# 02_Sensors.net
KiCad netlist of a schematic drawn in Altium Designer
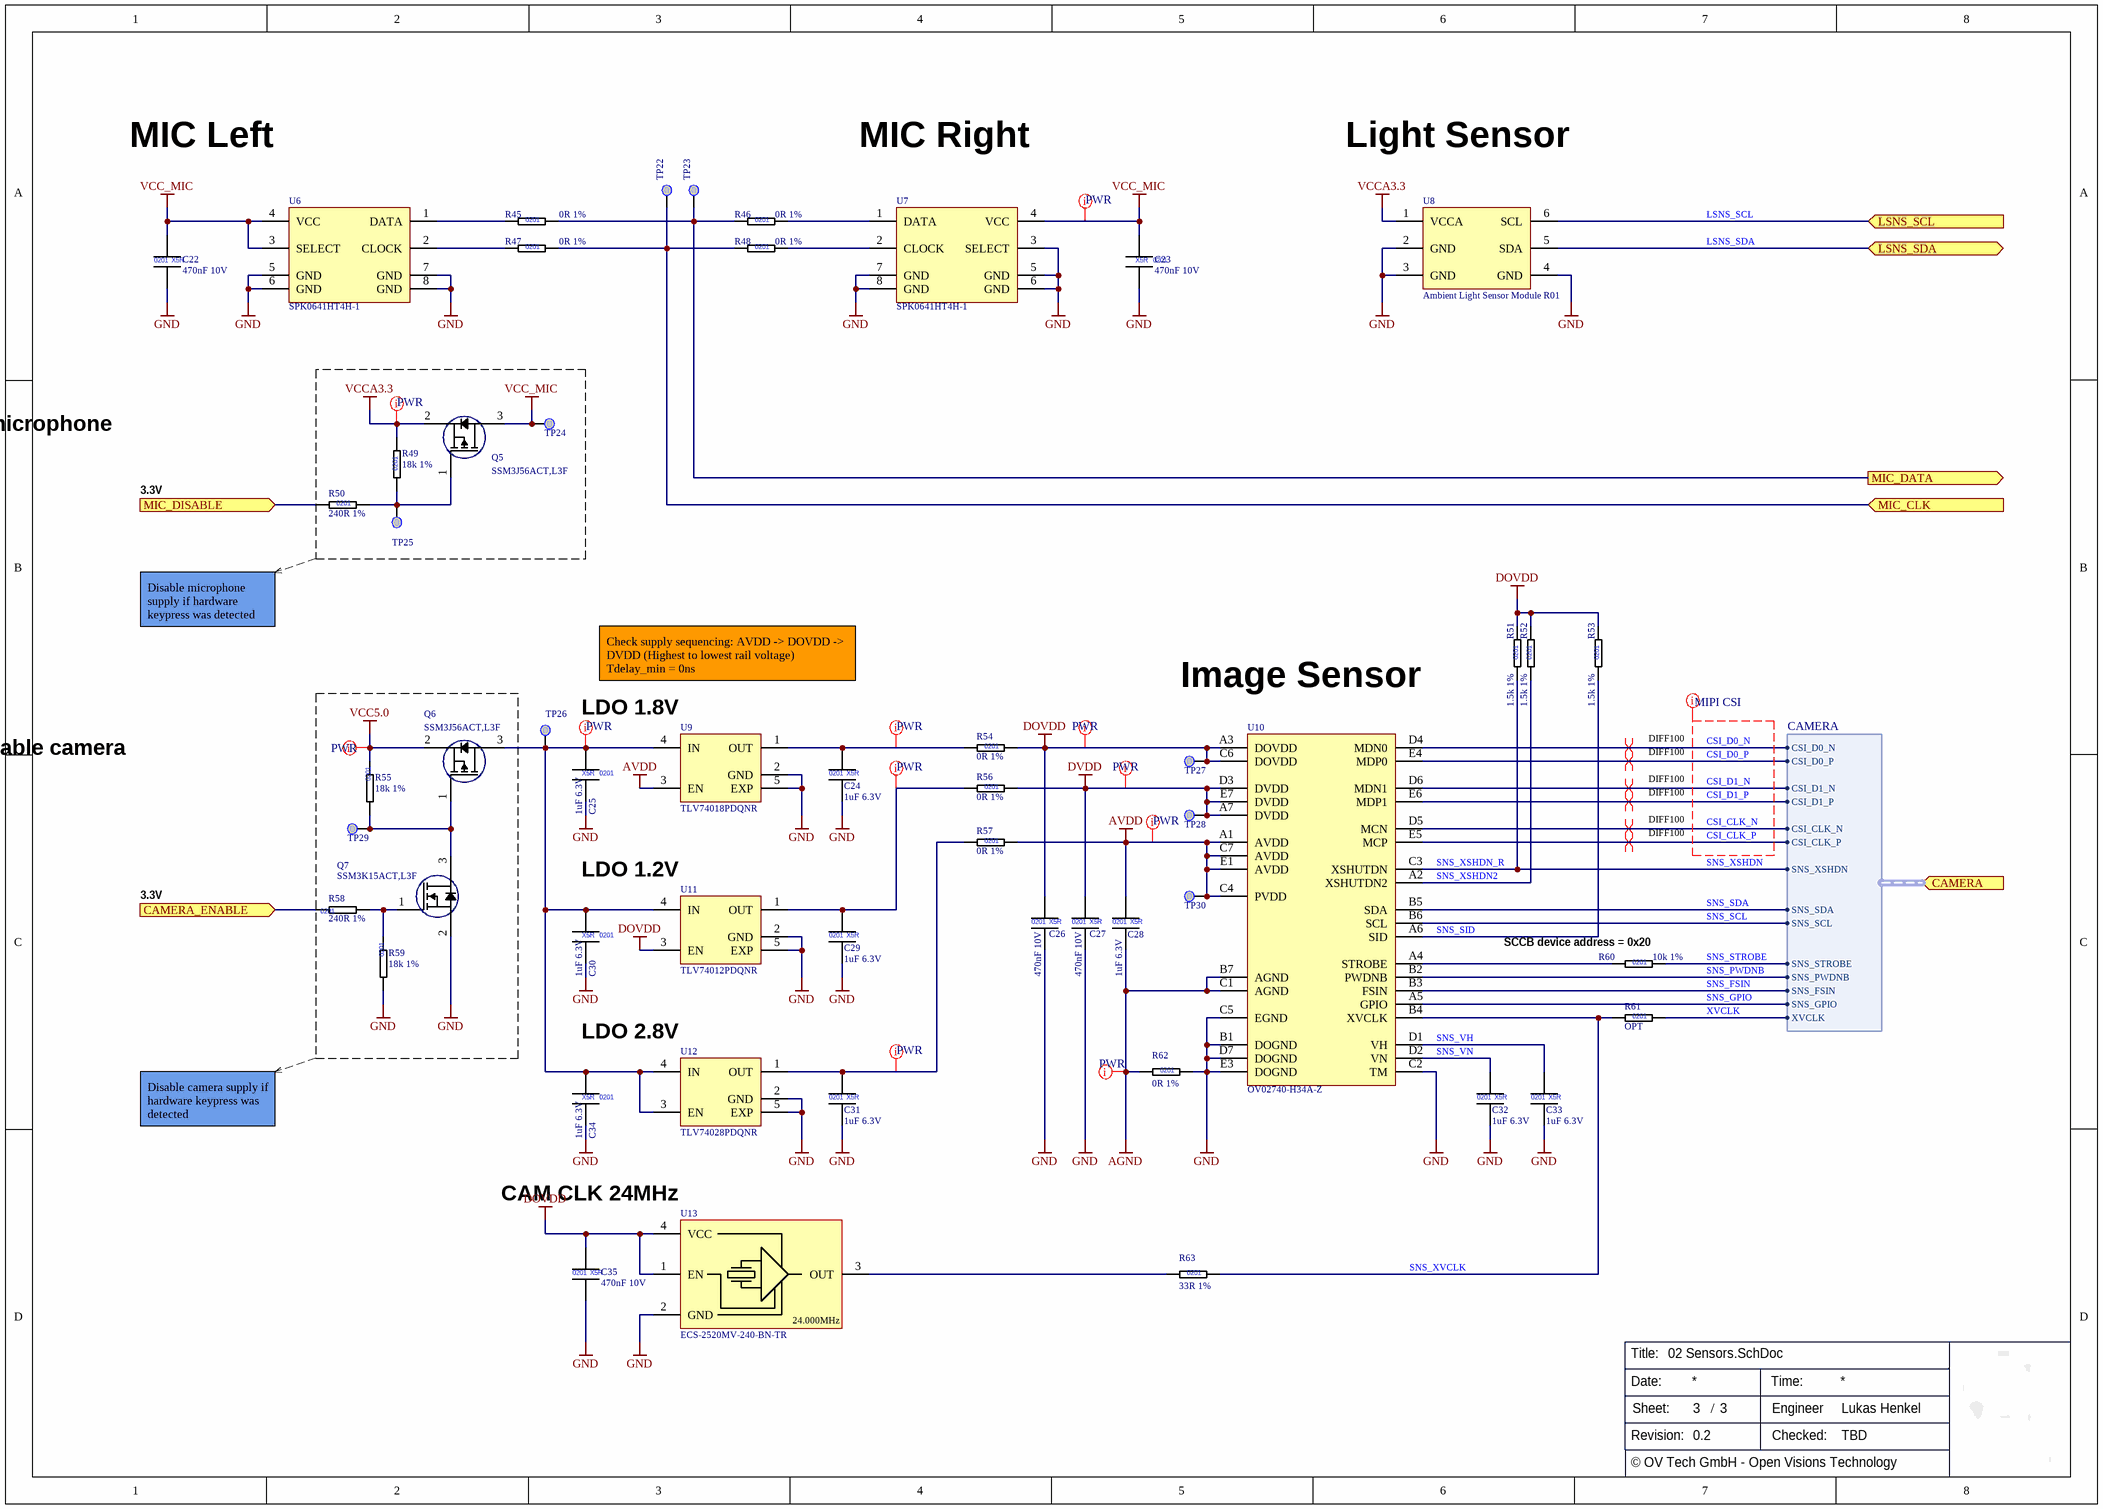
[diagram p0: 02 Sensors.SchDoc]

(export (version "E")
  (design (tool "Eeschema 10.0.6"))
  (components
    (comp (ref "C22")
      (value "470nF 10V")
      (footprint "QV_Cap:CAPC0603X03L")
      (description "Multilayer Ceramic Capacitors MLCC - SMD/SMT 0201 10VDC")
      (libsource (lib "QV_Cap") (part "CAP_0201_470nF_10V"))
    )
    (comp (ref "C23")
      (value "470nF 10V")
      (footprint "QV_Cap:CAPC0603X03L")
      (description "Multilayer Ceramic Capacitors MLCC - SMD/SMT 0201 10VDC")
      (libsource (lib "QV_Cap") (part "CAP_0201_470nF_10V"))
    )
    (comp (ref "C24")
      (value "1uF 6.3V")
      (footprint "QV_Cap:CAPC0603X03L")
      (description "Multilayer Ceramic Capacitors MLCC - SMD/SMT 0201 6.3VDC")
      (libsource (lib "QV_Cap") (part "CAP_0201_1uF_6.3V"))
    )
    (comp (ref "C25")
      (value "1uF 6.3V")
      (footprint "QV_Cap:CAPC0603X03L")
      (description "Multilayer Ceramic Capacitors MLCC - SMD/SMT 0201 6.3VDC")
      (libsource (lib "QV_Cap") (part "CAP_0201_1uF_6.3V"))
    )
    (comp (ref "C26")
      (value "470nF 10V")
      (footprint "QV_Cap:CAPC0603X03L")
      (description "Multilayer Ceramic Capacitors MLCC - SMD/SMT 0201 10VDC")
      (libsource (lib "QV_Cap") (part "CAP_0201_470nF_10V"))
    )
    (comp (ref "C27")
      (value "470nF 10V")
      (footprint "QV_Cap:CAPC0603X03L")
      (description "Multilayer Ceramic Capacitors MLCC - SMD/SMT 0201 10VDC")
      (libsource (lib "QV_Cap") (part "CAP_0201_470nF_10V"))
    )
    (comp (ref "C28")
      (value "1uF 6.3V")
      (footprint "QV_Cap:CAPC0603X03L")
      (description "Multilayer Ceramic Capacitors MLCC - SMD/SMT 0201 6.3VDC")
      (libsource (lib "QV_Cap") (part "CAP_0201_1uF_6.3V"))
    )
    (comp (ref "C29")
      (value "1uF 6.3V")
      (footprint "QV_Cap:CAPC0603X03L")
      (description "Multilayer Ceramic Capacitors MLCC - SMD/SMT 0201 6.3VDC")
      (libsource (lib "QV_Cap") (part "CAP_0201_1uF_6.3V"))
    )
    (comp (ref "C30")
      (value "1uF 6.3V")
      (footprint "QV_Cap:CAPC0603X03L")
      (description "Multilayer Ceramic Capacitors MLCC - SMD/SMT 0201 6.3VDC")
      (libsource (lib "QV_Cap") (part "CAP_0201_1uF_6.3V"))
    )
    (comp (ref "C31")
      (value "1uF 6.3V")
      (footprint "QV_Cap:CAPC0603X03L")
      (description "Multilayer Ceramic Capacitors MLCC - SMD/SMT 0201 6.3VDC")
      (libsource (lib "QV_Cap") (part "CAP_0201_1uF_6.3V"))
    )
    (comp (ref "C32")
      (value "1uF 6.3V")
      (footprint "QV_Cap:CAPC0603X03L")
      (description "Multilayer Ceramic Capacitors MLCC - SMD/SMT 0201 6.3VDC")
      (libsource (lib "QV_Cap") (part "CAP_0201_1uF_6.3V"))
    )
    (comp (ref "C33")
      (value "1uF 6.3V")
      (footprint "QV_Cap:CAPC0603X03L")
      (description "Multilayer Ceramic Capacitors MLCC - SMD/SMT 0201 6.3VDC")
      (libsource (lib "QV_Cap") (part "CAP_0201_1uF_6.3V"))
    )
    (comp (ref "C34")
      (value "1uF 6.3V")
      (footprint "QV_Cap:CAPC0603X03L")
      (description "Multilayer Ceramic Capacitors MLCC - SMD/SMT 0201 6.3VDC")
      (libsource (lib "QV_Cap") (part "CAP_0201_1uF_6.3V"))
    )
    (comp (ref "C35")
      (value "470nF 10V")
      (footprint "QV_Cap:CAPC0603X03L")
      (description "Multilayer Ceramic Capacitors MLCC - SMD/SMT 0201 10VDC")
      (libsource (lib "QV_Cap") (part "CAP_0201_470nF_10V"))
    )
    (comp (ref "Q5")
      (value "SSM3J56ACT,L3F")
      (footprint "QV_Trans:DFN65P100X50-3L")
      (description "MOSFET 20V SGL P-CH TRENCHMOS Logic Level")
      (libsource (lib "QV_Trans") (part "P-Channel MOSFET_SSM3J56ACT,L3F"))
    )
    (comp (ref "Q6")
      (value "SSM3J56ACT,L3F")
      (footprint "QV_Trans:DFN65P100X50-3L")
      (description "MOSFET 20V SGL P-CH TRENCHMOS Logic Level")
      (libsource (lib "QV_Trans") (part "P-Channel MOSFET_SSM3J56ACT,L3F"))
    )
    (comp (ref "Q7")
      (value "SSM3K15ACT,L3F")
      (footprint "QV_Trans:DFN65P100X50-3L")
      (description "MOSFET 30V SGL N-CH TRENCHMOS Logic Level")
      (libsource (lib "QV_Trans") (part "N-Channel MOSFET_SSM3K15ACT,L3F"))
    )
    (comp (ref "R45")
      (value "0R 1%")
      (footprint "QV_Res:RESC0603X03L")
      (description "Thick Film Resistors - SMD 0R OHM 1%")
      (libsource (lib "QV_res") (part "RES_0201_0R_1%"))
    )
    (comp (ref "R46")
      (value "0R 1%")
      (footprint "QV_Res:RESC0603X03L")
      (description "Thick Film Resistors - SMD 0R OHM 1%")
      (libsource (lib "QV_res") (part "RES_0201_0R_1%"))
    )
    (comp (ref "R47")
      (value "0R 1%")
      (footprint "QV_Res:RESC0603X03L")
      (description "Thick Film Resistors - SMD 0R OHM 1%")
      (libsource (lib "QV_res") (part "RES_0201_0R_1%"))
    )
    (comp (ref "R48")
      (value "0R 1%")
      (footprint "QV_Res:RESC0603X03L")
      (description "Thick Film Resistors - SMD 0R OHM 1%")
      (libsource (lib "QV_res") (part "RES_0201_0R_1%"))
    )
    (comp (ref "R49")
      (value "18k 1%")
      (footprint "QV_Res:RESC0603X03L")
      (description "Thick Film Resistors - SMD 18K OHM 1%")
      (libsource (lib "QV_res") (part "RES_0201_18k_1%"))
    )
    (comp (ref "R50")
      (value "240R 1%")
      (footprint "QV_Res:RESC0603X03L")
      (description "Thick Film Resistors - SMD 240 OHM 1%")
      (libsource (lib "QV_res") (part "RES_0201_240R_1%"))
    )
    (comp (ref "R51")
      (value "1.5k 1%")
      (footprint "QV_Res:RESC0603X03L")
      (description "Thick Film Resistors - SMD 1.5K OHM 1%")
      (libsource (lib "QV_res") (part "RES_0201_1.5k_1%"))
    )
    (comp (ref "R52")
      (value "1.5k 1%")
      (footprint "QV_Res:RESC0603X03L")
      (description "Thick Film Resistors - SMD 1.5K OHM 1%")
      (libsource (lib "QV_res") (part "RES_0201_1.5k_1%"))
    )
    (comp (ref "R53")
      (value "1.5k 1%")
      (footprint "QV_Res:RESC0603X03L")
      (description "Thick Film Resistors - SMD 1.5K OHM 1%")
      (libsource (lib "QV_res") (part "RES_0201_1.5k_1%"))
    )
    (comp (ref "R54")
      (value "0R 1%")
      (footprint "QV_Res:RESC0603X03L")
      (description "Thick Film Resistors - SMD 0R OHM 1%")
      (libsource (lib "QV_res") (part "RES_0201_0R_1%"))
    )
    (comp (ref "R55")
      (value "18k 1%")
      (footprint "QV_Res:RESC0603X03L")
      (description "Thick Film Resistors - SMD 18K OHM 1%")
      (libsource (lib "QV_res") (part "RES_0201_18k_1%"))
    )
    (comp (ref "R56")
      (value "0R 1%")
      (footprint "QV_Res:RESC0603X03L")
      (description "Thick Film Resistors - SMD 0R OHM 1%")
      (libsource (lib "QV_res") (part "RES_0201_0R_1%"))
    )
    (comp (ref "R57")
      (value "0R 1%")
      (footprint "QV_Res:RESC0603X03L")
      (description "Thick Film Resistors - SMD 0R OHM 1%")
      (libsource (lib "QV_res") (part "RES_0201_0R_1%"))
    )
    (comp (ref "R58")
      (value "240R 1%")
      (footprint "QV_Res:RESC0603X03L")
      (description "Thick Film Resistors - SMD 240 OHM 1%")
      (libsource (lib "QV_res") (part "RES_0201_240R_1%"))
    )
    (comp (ref "R59")
      (value "18k 1%")
      (footprint "QV_Res:RESC0603X03L")
      (description "Thick Film Resistors - SMD 18K OHM 1%")
      (libsource (lib "QV_res") (part "RES_0201_18k_1%"))
    )
    (comp (ref "R60")
      (value "10k 1%")
      (footprint "QV_Res:RESC0603X03L")
      (description "Thick Film Resistors - SMD 10K OHM 1%")
      (libsource (lib "QV_res") (part "RES_0201_10k_1%"))
    )
    (comp (ref "R61")
      (value "OPT")
      (footprint "QV_Res:RESC0603X03L")
      (description "Thick Film Resistors - SMD Optinal")
      (libsource (lib "QV_res") (part "RES_0201_OPT"))
    )
    (comp (ref "R62")
      (value "0R 1%")
      (footprint "QV_Res:RESC0603X03L")
      (description "Thick Film Resistors - SMD 0R OHM 1%")
      (libsource (lib "QV_res") (part "RES_0201_0R_1%"))
    )
    (comp (ref "R63")
      (value "33R 1%")
      (footprint "QV_Res:RESC0603X03L")
      (description "Thick Film Resistors - SMD 33R OHM 1%")
      (libsource (lib "QV_res") (part "RES_0201_33R_1%"))
    )
    (comp (ref "TP22")
      (value "Testpoint 0.5mm")
      (footprint "QV_ElectroMech:TP_0.50mm")
      (libsource (lib "QV_ElectroMech") (part "Testpoint 0.5mm"))
    )
    (comp (ref "TP23")
      (value "Testpoint 0.5mm")
      (footprint "QV_ElectroMech:TP_0.50mm")
      (libsource (lib "QV_ElectroMech") (part "Testpoint 0.5mm"))
    )
    (comp (ref "TP24")
      (value "Testpoint 0.5mm")
      (footprint "QV_ElectroMech:TP_0.50mm")
      (libsource (lib "QV_ElectroMech") (part "Testpoint 0.5mm"))
    )
    (comp (ref "TP25")
      (value "Testpoint 0.5mm")
      (footprint "QV_ElectroMech:TP_0.50mm")
      (libsource (lib "QV_ElectroMech") (part "Testpoint 0.5mm"))
    )
    (comp (ref "TP26")
      (value "Testpoint 0.5mm")
      (footprint "QV_ElectroMech:TP_0.50mm")
      (libsource (lib "QV_ElectroMech") (part "Testpoint 0.5mm"))
    )
    (comp (ref "TP27")
      (value "Testpoint 0.5mm")
      (footprint "QV_ElectroMech:TP_0.50mm")
      (libsource (lib "QV_ElectroMech") (part "Testpoint 0.5mm"))
    )
    (comp (ref "TP28")
      (value "Testpoint 0.5mm")
      (footprint "QV_ElectroMech:TP_0.50mm")
      (libsource (lib "QV_ElectroMech") (part "Testpoint 0.5mm"))
    )
    (comp (ref "TP29")
      (value "Testpoint 0.5mm")
      (footprint "QV_ElectroMech:TP_0.50mm")
      (libsource (lib "QV_ElectroMech") (part "Testpoint 0.5mm"))
    )
    (comp (ref "TP30")
      (value "Testpoint 0.5mm")
      (footprint "QV_ElectroMech:TP_0.50mm")
      (libsource (lib "QV_ElectroMech") (part "Testpoint 0.5mm"))
    )
    (comp (ref "U6")
      (value "SPK0641HT4H-1")
      (footprint "QV_Active:MIC_SPK0641HT4H-1")
      (description "Digital MEMS Microphone Top Port PDM SPK0641HT4H-1")
      (libsource (lib "QV_Active") (part "Digital Microphone PDM_SPK0641HT4H-1"))
    )
    (comp (ref "U7")
      (value "SPK0641HT4H-1")
      (footprint "QV_Active:MIC_SPK0641HT4H-1")
      (description "Digital MEMS Microphone Top Port PDM SPK0641HT4H-1")
      (libsource (lib "") (part "Digital Microphone PDM_SPK0641HT4H-1_1"))
    )
    (comp (ref "U8")
      (value "Ambient Light Sensor Module R01")
      (footprint "QV_ConMod:ABLS-R01-ambient light sensor module")
      (description "Custom Ambient Light Sensor Module with LGA Footprint")
      (libsource (lib "QV_ConMod") (part "Light Sensor Module R01"))
    )
    (comp (ref "U9")
      (value "TLV74018PDQNR")
      (footprint "QV_Linear:X2SON-DFN")
      (description "LDO voltage regulator 300mA X2SON")
      (libsource (lib "QV_Linear") (part "LDO 1.8V_TLV74018PDQNR"))
    )
    (comp (ref "U10")
      (value "OV02740-H34A-Z")
      (footprint "QV_Active:BGA34C53P7X5_386X292X388")
      (description "MIPI CSI Image Sensor 1080p 1/6\"")
      (libsource (lib "QV_Active") (part "Image Sensor_OV2740"))
    )
    (comp (ref "U11")
      (value "TLV74012PDQNR")
      (footprint "QV_Linear:X2SON-DFN")
      (description "LDO voltage regulator 300mA X2SON")
      (libsource (lib "QV_Linear") (part "LDO 1.2V_TLV74012PDQNR"))
    )
    (comp (ref "U12")
      (value "TLV74028PDQNR")
      (footprint "QV_Linear:X2SON-DFN")
      (description "LDO voltage regulator 300mA X2SON")
      (libsource (lib "QV_Linear") (part "LDO 2.8V_TLV74028PDQNR"))
    )
    (comp (ref "U13")
      (value "ECS-2520MV-240-BN-TR")
      (footprint "QV_Timer:Oscillator_ECS-2520MV")
      (description "Crystal Oscillator 2520 miniature SMD package")
      (libsource (lib "QV_Timer") (part "Crystal Oscillator_ECS-2520MV-240-BN-TR"))
    )
  )
  (nets
    (net (code "2") (name "/CAMERA_ENABLE") (class "Default")
      (node (ref "R58") (pin "1") (pinfunction "1_1") (pintype "passive"))
    )
    (net (code "3") (name "/CSI_CLK_N") (class "Default")
      (node (ref "U10") (pin "D5") (pinfunction "MCN_D5") (pintype "passive"))
    )
    (net (code "4") (name "/CSI_CLK_P") (class "Default")
      (node (ref "U10") (pin "E5") (pinfunction "MCP_E5") (pintype "passive"))
    )
    (net (code "5") (name "/CSI_D0_N") (class "Default")
      (node (ref "U10") (pin "D4") (pinfunction "MDN0_D4") (pintype "passive"))
    )
    (net (code "6") (name "/CSI_D0_P") (class "Default")
      (node (ref "U10") (pin "E4") (pinfunction "MDP0_E4") (pintype "passive"))
    )
    (net (code "7") (name "/CSI_D1_N") (class "Default")
      (node (ref "U10") (pin "D6") (pinfunction "MDN1_D6") (pintype "passive"))
    )
    (net (code "8") (name "/CSI_D1_P") (class "Default")
      (node (ref "U10") (pin "E6") (pinfunction "MDP1_E6") (pintype "passive"))
    )
    (net (code "9") (name "/LSNS_SCL") (class "Default")
      (node (ref "U8") (pin "6") (pinfunction "SCL_6") (pintype "passive"))
    )
    (net (code "10") (name "/LSNS_SDA") (class "Default")
      (node (ref "U8") (pin "5") (pinfunction "SDA_5") (pintype "passive"))
    )
    (net (code "11") (name "/MIC_CLK") (class "Default")
      (node (ref "R47") (pin "2") (pinfunction "2_2") (pintype "passive"))
      (node (ref "R48") (pin "1") (pinfunction "1_1") (pintype "passive"))
      (node (ref "TP22") (pin "TP") (pinfunction "TP_TP") (pintype "passive"))
    )
    (net (code "12") (name "/MIC_DATA") (class "Default")
      (node (ref "R45") (pin "2") (pinfunction "2_2") (pintype "passive"))
      (node (ref "R46") (pin "1") (pinfunction "1_1") (pintype "passive"))
      (node (ref "TP23") (pin "TP") (pinfunction "TP_TP") (pintype "passive"))
    )
    (net (code "13") (name "/MIC_DISABLE") (class "Default")
      (node (ref "R50") (pin "1") (pinfunction "1_1") (pintype "passive"))
    )
    (net (code "14") (name "/SNS_FSIN") (class "Default")
      (node (ref "U10") (pin "B3") (pinfunction "FSIN_B3") (pintype "passive"))
    )
    (net (code "15") (name "/SNS_GPIO") (class "Default")
      (node (ref "U10") (pin "A5") (pinfunction "GPIO_A5") (pintype "passive"))
    )
    (net (code "16") (name "/SNS_PWDNB") (class "Default")
      (node (ref "U10") (pin "B2") (pinfunction "PWDNB_B2") (pintype "passive"))
    )
    (net (code "17") (name "/SNS_SCL") (class "Default")
      (node (ref "U10") (pin "B6") (pinfunction "SCL_B6") (pintype "passive"))
    )
    (net (code "18") (name "/SNS_SDA") (class "Default")
      (node (ref "U10") (pin "B5") (pinfunction "SDA_B5") (pintype "passive"))
    )
    (net (code "19") (name "/SNS_SID") (class "Default")
      (node (ref "R53") (pin "1") (pinfunction "1_1") (pintype "passive"))
      (node (ref "U10") (pin "A6") (pinfunction "SID_A6") (pintype "passive"))
    )
    (net (code "20") (name "/SNS_STROBE") (class "Default")
      (node (ref "R60") (pin "2") (pinfunction "2_2") (pintype "passive"))
    )
    (net (code "21") (name "/SNS_VH") (class "Default")
      (node (ref "C33") (pin "1") (pinfunction "1_1") (pintype "passive"))
      (node (ref "U10") (pin "D1") (pinfunction "VH_D1") (pintype "passive"))
    )
    (net (code "22") (name "/SNS_VN") (class "Default")
      (node (ref "C32") (pin "1") (pinfunction "1_1") (pintype "passive"))
      (node (ref "U10") (pin "D2") (pinfunction "VN_D2") (pintype "passive"))
    )
    (net (code "23") (name "/SNS_XSHDN") (class "Default")
      (node (ref "R51") (pin "1") (pinfunction "1_1") (pintype "passive"))
      (node (ref "U10") (pin "C3") (pinfunction "XSHUTDN_C3") (pintype "passive"))
    )
    (net (code "24") (name "/SNS_XSHDN2") (class "Default")
      (node (ref "R52") (pin "1") (pinfunction "1_1") (pintype "passive"))
      (node (ref "U10") (pin "A2") (pinfunction "XSHUTDN2_A2") (pintype "passive"))
    )
    (net (code "25") (name "/SNS_XVCLK") (class "Default")
      (node (ref "R61") (pin "1") (pinfunction "1_1") (pintype "passive"))
      (node (ref "R63") (pin "2") (pinfunction "2_2") (pintype "passive"))
      (node (ref "U10") (pin "B4") (pinfunction "XVCLK_B4") (pintype "passive"))
    )
    (net (code "26") (name "/XVCLK") (class "Default")
      (node (ref "R61") (pin "2") (pinfunction "2_2") (pintype "passive"))
    )
    (net (code "28") (name "AGND") (class "Default")
      (node (ref "C28") (pin "2") (pinfunction "2_2") (pintype "passive"))
      (node (ref "R62") (pin "1") (pinfunction "1_1") (pintype "passive"))
      (node (ref "U10") (pin "B7") (pinfunction "AGND_B7") (pintype "passive"))
      (node (ref "U10") (pin "C1") (pinfunction "AGND_C1") (pintype "passive"))
    )
    (net (code "29") (name "AVDD") (class "Default")
      (node (ref "C28") (pin "1") (pinfunction "1_1") (pintype "passive"))
      (node (ref "R57") (pin "2") (pinfunction "2_2") (pintype "passive"))
      (node (ref "TP30") (pin "TP") (pinfunction "TP_TP") (pintype "passive"))
      (node (ref "U10") (pin "A1") (pinfunction "AVDD_A1") (pintype "passive"))
      (node (ref "U10") (pin "C4") (pinfunction "PVDD_C4") (pintype "passive"))
      (node (ref "U10") (pin "C7") (pinfunction "AVDD_C7") (pintype "passive"))
      (node (ref "U10") (pin "E1") (pinfunction "AVDD_E1") (pintype "passive"))
      (node (ref "U9") (pin "3") (pinfunction "EN_3") (pintype "passive"))
    )
    (net (code "30") (name "DOVDD") (class "Default")
      (node (ref "C26") (pin "1") (pinfunction "1_1") (pintype "passive"))
      (node (ref "C35") (pin "1") (pinfunction "1_1") (pintype "passive"))
      (node (ref "R51") (pin "2") (pinfunction "2_2") (pintype "passive"))
      (node (ref "R52") (pin "2") (pinfunction "2_2") (pintype "passive"))
      (node (ref "R53") (pin "2") (pinfunction "2_2") (pintype "passive"))
      (node (ref "R54") (pin "2") (pinfunction "2_2") (pintype "passive"))
      (node (ref "TP27") (pin "TP") (pinfunction "TP_TP") (pintype "passive"))
      (node (ref "U10") (pin "A3") (pinfunction "DOVDD_A3") (pintype "passive"))
      (node (ref "U10") (pin "C6") (pinfunction "DOVDD_C6") (pintype "passive"))
      (node (ref "U11") (pin "3") (pinfunction "EN_3") (pintype "passive"))
      (node (ref "U13") (pin "1") (pinfunction "EN_1") (pintype "passive"))
      (node (ref "U13") (pin "4") (pinfunction "VCC_4") (pintype "passive"))
    )
    (net (code "31") (name "DVDD") (class "Default")
      (node (ref "C27") (pin "1") (pinfunction "1_1") (pintype "passive"))
      (node (ref "R56") (pin "2") (pinfunction "2_2") (pintype "passive"))
      (node (ref "TP28") (pin "TP") (pinfunction "TP_TP") (pintype "passive"))
      (node (ref "U10") (pin "A7") (pinfunction "DVDD_A7") (pintype "passive"))
      (node (ref "U10") (pin "D3") (pinfunction "DVDD_D3") (pintype "passive"))
      (node (ref "U10") (pin "E7") (pinfunction "DVDD_E7") (pintype "passive"))
    )
    (net (code "32") (name "GND") (class "Default")
      (node (ref "C22") (pin "2") (pinfunction "2_2") (pintype "passive"))
      (node (ref "C23") (pin "2") (pinfunction "2_2") (pintype "passive"))
      (node (ref "C24") (pin "2") (pinfunction "2_2") (pintype "passive"))
      (node (ref "C25") (pin "2") (pinfunction "2_2") (pintype "passive"))
      (node (ref "C26") (pin "2") (pinfunction "2_2") (pintype "passive"))
      (node (ref "C27") (pin "2") (pinfunction "2_2") (pintype "passive"))
      (node (ref "C29") (pin "2") (pinfunction "2_2") (pintype "passive"))
      (node (ref "C30") (pin "2") (pinfunction "2_2") (pintype "passive"))
      (node (ref "C31") (pin "2") (pinfunction "2_2") (pintype "passive"))
      (node (ref "C32") (pin "2") (pinfunction "2_2") (pintype "passive"))
      (node (ref "C33") (pin "2") (pinfunction "2_2") (pintype "passive"))
      (node (ref "C34") (pin "2") (pinfunction "2_2") (pintype "passive"))
      (node (ref "C35") (pin "2") (pinfunction "2_2") (pintype "passive"))
      (node (ref "Q7") (pin "2") (pinfunction "S_2") (pintype "passive"))
      (node (ref "R59") (pin "2") (pinfunction "2_2") (pintype "passive"))
      (node (ref "R62") (pin "2") (pinfunction "2_2") (pintype "passive"))
      (node (ref "U10") (pin "B1") (pinfunction "DOGND_B1") (pintype "passive"))
      (node (ref "U10") (pin "C2") (pinfunction "TM_C2") (pintype "passive"))
      (node (ref "U10") (pin "C5") (pinfunction "EGND_C5") (pintype "passive"))
      (node (ref "U10") (pin "D7") (pinfunction "DOGND_D7") (pintype "passive"))
      (node (ref "U10") (pin "E3") (pinfunction "DOGND_E3") (pintype "passive"))
      (node (ref "U11") (pin "2") (pinfunction "GND_2") (pintype "passive"))
      (node (ref "U11") (pin "5") (pinfunction "EXP_5") (pintype "passive"))
      (node (ref "U12") (pin "2") (pinfunction "GND_2") (pintype "passive"))
      (node (ref "U12") (pin "5") (pinfunction "EXP_5") (pintype "passive"))
      (node (ref "U13") (pin "2") (pinfunction "GND_2") (pintype "passive"))
      (node (ref "U6") (pin "5") (pinfunction "GND_5") (pintype "passive"))
      (node (ref "U6") (pin "6") (pinfunction "GND_6") (pintype "passive"))
      (node (ref "U6") (pin "7") (pinfunction "GND_7") (pintype "passive"))
      (node (ref "U6") (pin "8") (pinfunction "GND_8") (pintype "passive"))
      (node (ref "U7") (pin "3") (pinfunction "SELECT_3") (pintype "passive"))
      (node (ref "U7") (pin "5") (pinfunction "GND_5") (pintype "passive"))
      (node (ref "U7") (pin "6") (pinfunction "GND_6") (pintype "passive"))
      (node (ref "U7") (pin "7") (pinfunction "GND_7") (pintype "passive"))
      (node (ref "U7") (pin "8") (pinfunction "GND_8") (pintype "passive"))
      (node (ref "U8") (pin "2") (pinfunction "GND_2") (pintype "passive"))
      (node (ref "U8") (pin "3") (pinfunction "GND_3") (pintype "passive"))
      (node (ref "U8") (pin "4") (pinfunction "GND_4") (pintype "passive"))
      (node (ref "U9") (pin "2") (pinfunction "GND_2") (pintype "passive"))
      (node (ref "U9") (pin "5") (pinfunction "EXP_5") (pintype "passive"))
    )
    (net (code "33") (name "Net-(Q5-G)") (class "Default")
      (node (ref "Q5") (pin "1") (pinfunction "G_1") (pintype "passive"))
      (node (ref "R49") (pin "1") (pinfunction "1_1") (pintype "passive"))
      (node (ref "R50") (pin "2") (pinfunction "2_2") (pintype "passive"))
      (node (ref "TP25") (pin "TP") (pinfunction "TP_TP") (pintype "passive"))
    )
    (net (code "34") (name "Net-(Q6-D)") (class "Default")
      (node (ref "C25") (pin "1") (pinfunction "1_1") (pintype "passive"))
      (node (ref "C30") (pin "1") (pinfunction "1_1") (pintype "passive"))
      (node (ref "C34") (pin "1") (pinfunction "1_1") (pintype "passive"))
      (node (ref "Q6") (pin "3") (pinfunction "D_3") (pintype "passive"))
      (node (ref "TP26") (pin "TP") (pinfunction "TP_TP") (pintype "passive"))
      (node (ref "U11") (pin "4") (pinfunction "IN_4") (pintype "passive"))
      (node (ref "U12") (pin "3") (pinfunction "EN_3") (pintype "passive"))
      (node (ref "U12") (pin "4") (pinfunction "IN_4") (pintype "passive"))
      (node (ref "U9") (pin "4") (pinfunction "IN_4") (pintype "passive"))
    )
    (net (code "35") (name "Net-(Q6-G)") (class "Default")
      (node (ref "Q6") (pin "1") (pinfunction "G_1") (pintype "passive"))
      (node (ref "Q7") (pin "3") (pinfunction "D_3") (pintype "passive"))
      (node (ref "R55") (pin "2") (pinfunction "2_2") (pintype "passive"))
      (node (ref "TP29") (pin "TP") (pinfunction "TP_TP") (pintype "passive"))
    )
    (net (code "36") (name "Net-(Q7-G)") (class "Default")
      (node (ref "Q7") (pin "1") (pinfunction "G_1") (pintype "passive"))
      (node (ref "R58") (pin "2") (pinfunction "2_2") (pintype "passive"))
      (node (ref "R59") (pin "1") (pinfunction "1_1") (pintype "passive"))
    )
    (net (code "37") (name "Net-(U6-CLOCK)") (class "Default")
      (node (ref "R47") (pin "1") (pinfunction "1_1") (pintype "passive"))
      (node (ref "U6") (pin "2") (pinfunction "CLOCK_2") (pintype "passive"))
    )
    (net (code "38") (name "Net-(U6-DATA)") (class "Default")
      (node (ref "R45") (pin "1") (pinfunction "1_1") (pintype "passive"))
      (node (ref "U6") (pin "1") (pinfunction "DATA_1") (pintype "passive"))
    )
    (net (code "39") (name "Net-(U7-CLOCK)") (class "Default")
      (node (ref "R48") (pin "2") (pinfunction "2_2") (pintype "passive"))
      (node (ref "U7") (pin "2") (pinfunction "CLOCK_2") (pintype "passive"))
    )
    (net (code "40") (name "Net-(U7-DATA)") (class "Default")
      (node (ref "R46") (pin "2") (pinfunction "2_2") (pintype "passive"))
      (node (ref "U7") (pin "1") (pinfunction "DATA_1") (pintype "passive"))
    )
    (net (code "41") (name "Net-(U9-OUT)") (class "Default")
      (node (ref "C24") (pin "1") (pinfunction "1_1") (pintype "passive"))
      (node (ref "R54") (pin "1") (pinfunction "1_1") (pintype "passive"))
      (node (ref "U9") (pin "1") (pinfunction "OUT_1") (pintype "passive"))
    )
    (net (code "42") (name "Net-(U10-STROBE)") (class "Default")
      (node (ref "R60") (pin "1") (pinfunction "1_1") (pintype "passive"))
      (node (ref "U10") (pin "A4") (pinfunction "STROBE_A4") (pintype "passive"))
    )
    (net (code "43") (name "Net-(U11-OUT)") (class "Default")
      (node (ref "C29") (pin "1") (pinfunction "1_1") (pintype "passive"))
      (node (ref "R56") (pin "1") (pinfunction "1_1") (pintype "passive"))
      (node (ref "U11") (pin "1") (pinfunction "OUT_1") (pintype "passive"))
    )
    (net (code "44") (name "Net-(U12-OUT)") (class "Default")
      (node (ref "C31") (pin "1") (pinfunction "1_1") (pintype "passive"))
      (node (ref "R57") (pin "1") (pinfunction "1_1") (pintype "passive"))
      (node (ref "U12") (pin "1") (pinfunction "OUT_1") (pintype "passive"))
    )
    (net (code "45") (name "Net-(U13-OUT)") (class "Default")
      (node (ref "R63") (pin "1") (pinfunction "1_1") (pintype "passive"))
      (node (ref "U13") (pin "3") (pinfunction "OUT_3") (pintype "passive"))
    )
    (net (code "46") (name "VCC5.0") (class "Default")
      (node (ref "Q6") (pin "2") (pinfunction "S_2") (pintype "passive"))
      (node (ref "R55") (pin "1") (pinfunction "1_1") (pintype "passive"))
    )
    (net (code "47") (name "VCCA3.3") (class "Default")
      (node (ref "Q5") (pin "2") (pinfunction "S_2") (pintype "passive"))
      (node (ref "R49") (pin "2") (pinfunction "2_2") (pintype "passive"))
      (node (ref "U8") (pin "1") (pinfunction "VCCA_1") (pintype "passive"))
    )
    (net (code "48") (name "VCC_MIC") (class "Default")
      (node (ref "C22") (pin "1") (pinfunction "1_1") (pintype "passive"))
      (node (ref "C23") (pin "1") (pinfunction "1_1") (pintype "passive"))
      (node (ref "Q5") (pin "3") (pinfunction "D_3") (pintype "passive"))
      (node (ref "TP24") (pin "TP") (pinfunction "TP_TP") (pintype "passive"))
      (node (ref "U6") (pin "3") (pinfunction "SELECT_3") (pintype "passive"))
      (node (ref "U6") (pin "4") (pinfunction "VCC_4") (pintype "passive"))
      (node (ref "U7") (pin "4") (pinfunction "VCC_4") (pintype "passive"))
    )
  )
)
